# Clock.net
KiCad netlist of a schematic drawn in EAGLE
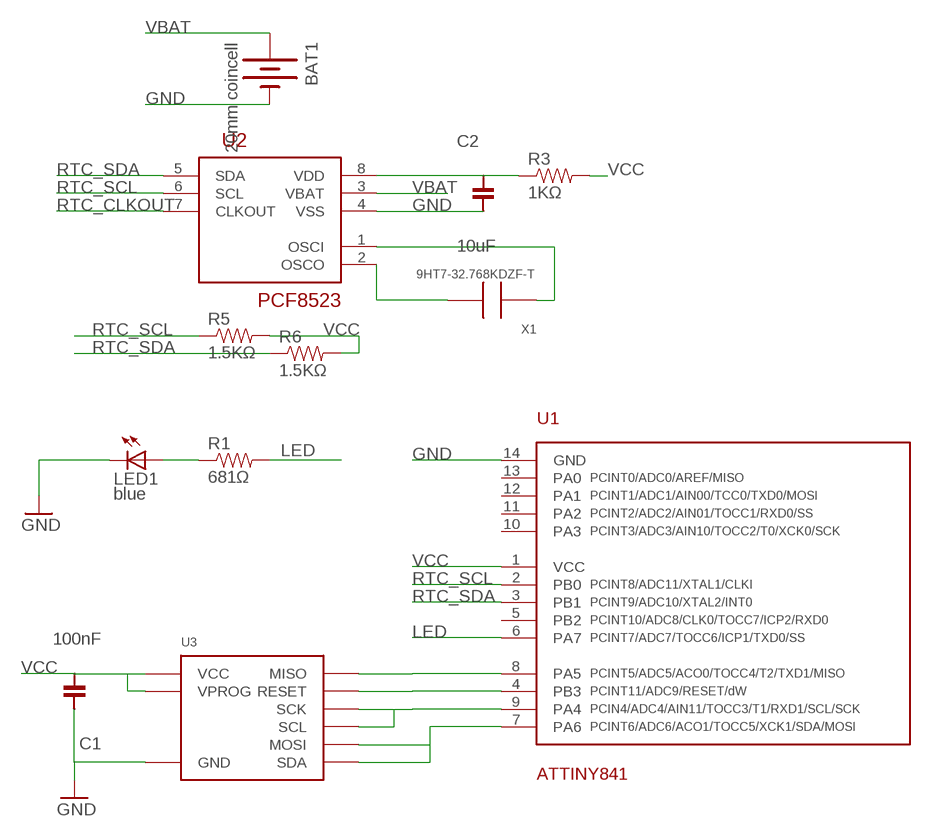
[diagram p0: schematic, sheet 1]

(export (version "E")
  (design (tool "Eeschema 10.0.6"))
  (components
    (comp (ref "BAT1")
      (value "20mm coincell")
      (footprint "eagle-import:BATTCON_20MM_4LEGS")
      (fields (field (name "PARTNUM") "BAT-HLD-001"))
      (libsource (lib "eagle-import") (part "BATTERY20MM_4LEGS"))
    )
    (comp (ref "C1")
      (value "100nF")
      (footprint "eagle-import:0603")
      (fields (field (name "PARTNUM") "C0603C104K5RACTU"))
      (libsource (lib "eagle-import") (part "CAPACITOR-100NF"))
    )
    (comp (ref "C2")
      (value "10uF")
      (footprint "eagle-import:0603")
      (fields (field (name "PARTNUM") "GRM188R60J106ME47D"))
      (libsource (lib "eagle-import") (part "CAPACITOR-10UF"))
    )
    (comp (ref "LED1")
      (value "blue")
      (footprint "eagle-import:0805-LED")
      (fields (field (name "PARTNUM") "LTST-C171TBKT"))
      (libsource (lib "eagle-import") (part "LED-0805-BLUE"))
    )
    (comp (ref "R1")
      (value "681Ω")
      (footprint "eagle-import:0603")
      (fields (field (name "PARTNUM") "ERJ-3EKF6810V"))
      (libsource (lib "eagle-import") (part "RESISTOR-681Ω"))
    )
    (comp (ref "R3")
      (value "1KΩ")
      (footprint "eagle-import:0603")
      (fields (field (name "PARTNUM") "ERJ-3EKF1001V"))
      (libsource (lib "eagle-import") (part "RESISTOR-1KΩ"))
    )
    (comp (ref "R5")
      (value "1.5KΩ")
      (footprint "eagle-import:0603")
      (fields (field (name "PARTNUM") "ERJ-3EKF1501V"))
      (libsource (lib "eagle-import") (part "RESISTOR-1.5KΩ"))
    )
    (comp (ref "R6")
      (value "1.5KΩ")
      (footprint "eagle-import:0603")
      (fields (field (name "PARTNUM") "ERJ-3EKF1501V"))
      (libsource (lib "eagle-import") (part "RESISTOR-1.5KΩ"))
    )
    (comp (ref "U1")
      (value "ATTINY841")
      (footprint "eagle-import:SOIC-14")
      (fields (field (name "PARTNUM") "ATTINY841-SSUR"))
      (libsource (lib "eagle-import") (part "ATTINY841"))
    )
    (comp (ref "U2")
      (value "PCF8523")
      (footprint "eagle-import:SOIC-8")
      (libsource (lib "eagle-import") (part "PCF8523"))
    )
    (comp (ref "U3")
      (value "EXCLUDE")
      (footprint "eagle-import:DEVICE-PCB")
      (libsource (lib "eagle-import") (part "DEVICE-PCB"))
    )
    (comp (ref "X1")
      (value "9HT7-32.768KDZF-T")
      (footprint "eagle-import:CRYSTAL-ABS25")
      (libsource (lib "eagle-import") (part "CRYSTALABS25"))
    )
  )
  (nets
    (net (code "1") (name "/LED") (class "Default")
      (node (ref "R1") (pin "2") (pinfunction "2_2") (pintype "passive"))
      (node (ref "U1") (pin "6") (pinfunction "PA7_6") (pintype "bidirectional"))
    )
    (net (code "2") (name "/MISO") (class "Default")
      (node (ref "U1") (pin "8") (pinfunction "PA5_8") (pintype "bidirectional"))
      (node (ref "U3") (pin "PROG3") (pinfunction "MISO_PROG3") (pintype "bidirectional"))
    )
    (net (code "3") (name "/RESET") (class "Default")
      (node (ref "U1") (pin "4") (pinfunction "PB3_4") (pintype "bidirectional"))
      (node (ref "U3") (pin "PROG1") (pinfunction "RESET_PROG1") (pintype "bidirectional"))
    )
    (net (code "4") (name "/RTC_CLKOUT") (class "Default")
      (node (ref "U2") (pin "7") (pinfunction "CLKOUT_7") (pintype "bidirectional"))
    )
    (net (code "5") (name "/RTC_SCL") (class "Default")
      (node (ref "R5") (pin "1") (pinfunction "1_1") (pintype "passive"))
      (node (ref "U1") (pin "2") (pinfunction "PB0_2") (pintype "bidirectional"))
      (node (ref "U2") (pin "6") (pinfunction "SCL_6") (pintype "bidirectional"))
    )
    (net (code "6") (name "/RTC_SDA") (class "Default")
      (node (ref "R6") (pin "1") (pinfunction "1_1") (pintype "passive"))
      (node (ref "U1") (pin "3") (pinfunction "PB1_3") (pintype "bidirectional"))
      (node (ref "U2") (pin "5") (pinfunction "SDA_5") (pintype "bidirectional"))
    )
    (net (code "7") (name "/SCL{slash}SCK") (class "Default")
      (node (ref "U1") (pin "9") (pinfunction "PA4_9") (pintype "bidirectional"))
      (node (ref "U3") (pin "BUS3") (pinfunction "SCL_BUS3") (pintype "bidirectional"))
      (node (ref "U3") (pin "PROG2") (pinfunction "SCK_PROG2") (pintype "bidirectional"))
    )
    (net (code "8") (name "/VBAT") (class "Default")
      (node (ref "BAT1") (pin "1") (pinfunction "+_1") (pintype "power_in"))
      (node (ref "U2") (pin "3") (pinfunction "VBAT_3") (pintype "bidirectional"))
    )
    (net (code "9") (name "/VCC") (class "Default")
      (node (ref "C1") (pin "2") (pinfunction "2_2") (pintype "passive"))
      (node (ref "R3") (pin "2") (pinfunction "2_2") (pintype "passive"))
      (node (ref "R5") (pin "2") (pinfunction "2_2") (pintype "passive"))
      (node (ref "R6") (pin "2") (pinfunction "2_2") (pintype "passive"))
      (node (ref "U1") (pin "1") (pinfunction "VCC_1") (pintype "bidirectional"))
      (node (ref "U3") (pin "BUS2") (pinfunction "VCC_BUS2") (pintype "bidirectional"))
      (node (ref "U3") (pin "PROG0") (pinfunction "VPROG_PROG0") (pintype "bidirectional"))
    )
    (net (code "10") (name "GND") (class "Default")
      (node (ref "BAT1") (pin "2") (pinfunction "-_2") (pintype "power_in"))
      (node (ref "C1") (pin "1") (pinfunction "1_1") (pintype "passive"))
      (node (ref "C2") (pin "2") (pinfunction "2_2") (pintype "passive"))
      (node (ref "LED1") (pin "C") (pinfunction "C_C") (pintype "passive"))
      (node (ref "U1") (pin "14") (pinfunction "GND_14") (pintype "bidirectional"))
      (node (ref "U2") (pin "4") (pinfunction "VSS_4") (pintype "bidirectional"))
      (node (ref "U3") (pin "BUS0") (pinfunction "GND_BUS0") (pintype "bidirectional"))
    )
    (net (code "11") (name "Net-(LED1-PadA)") (class "Default")
      (node (ref "LED1") (pin "A") (pinfunction "A_A") (pintype "passive"))
      (node (ref "R1") (pin "1") (pinfunction "1_1") (pintype "passive"))
    )
    (net (code "12") (name "Net-(U1-PA6)") (class "Default")
      (node (ref "U1") (pin "7") (pinfunction "PA6_7") (pintype "bidirectional"))
      (node (ref "U3") (pin "BUS1") (pinfunction "SDA_BUS1") (pintype "bidirectional"))
      (node (ref "U3") (pin "PROG4") (pinfunction "MOSI_PROG4") (pintype "bidirectional"))
    )
    (net (code "13") (name "Net-(U2-OSCI)") (class "Default")
      (node (ref "U2") (pin "1") (pinfunction "OSCI_1") (pintype "bidirectional"))
      (node (ref "X1") (pin "P$1") (pinfunction "P$1_P$1") (pintype "bidirectional"))
    )
    (net (code "14") (name "Net-(U2-OSCO)") (class "Default")
      (node (ref "U2") (pin "2") (pinfunction "OSCO_2") (pintype "bidirectional"))
      (node (ref "X1") (pin "P$4") (pinfunction "P$2_P$4") (pintype "bidirectional"))
    )
    (net (code "15") (name "Net-(U2-VDD)") (class "Default")
      (node (ref "C2") (pin "1") (pinfunction "1_1") (pintype "passive"))
      (node (ref "R3") (pin "1") (pinfunction "1_1") (pintype "passive"))
      (node (ref "U2") (pin "8") (pinfunction "VDD_8") (pintype "bidirectional"))
    )
    (net (code "16") (name "unconnected-(U1-PA0-Pad13)") (class "Default")
      (node (ref "U1") (pin "13") (pinfunction "PA0_13") (pintype "bidirectional"))
    )
    (net (code "17") (name "unconnected-(U1-PA1-Pad12)") (class "Default")
      (node (ref "U1") (pin "12") (pinfunction "PA1_12") (pintype "bidirectional"))
    )
    (net (code "18") (name "unconnected-(U1-PA2-Pad11)") (class "Default")
      (node (ref "U1") (pin "11") (pinfunction "PA2_11") (pintype "bidirectional"))
    )
    (net (code "19") (name "unconnected-(U1-PA3-Pad10)") (class "Default")
      (node (ref "U1") (pin "10") (pinfunction "PA3_10") (pintype "bidirectional"))
    )
    (net (code "20") (name "unconnected-(U1-PB2-Pad5)") (class "Default")
      (node (ref "U1") (pin "5") (pinfunction "PB2_5") (pintype "bidirectional"))
    )
  )
)
